# RPi_SPI_outputs_v01.net
KiCad netlist of a schematic drawn in EAGLE
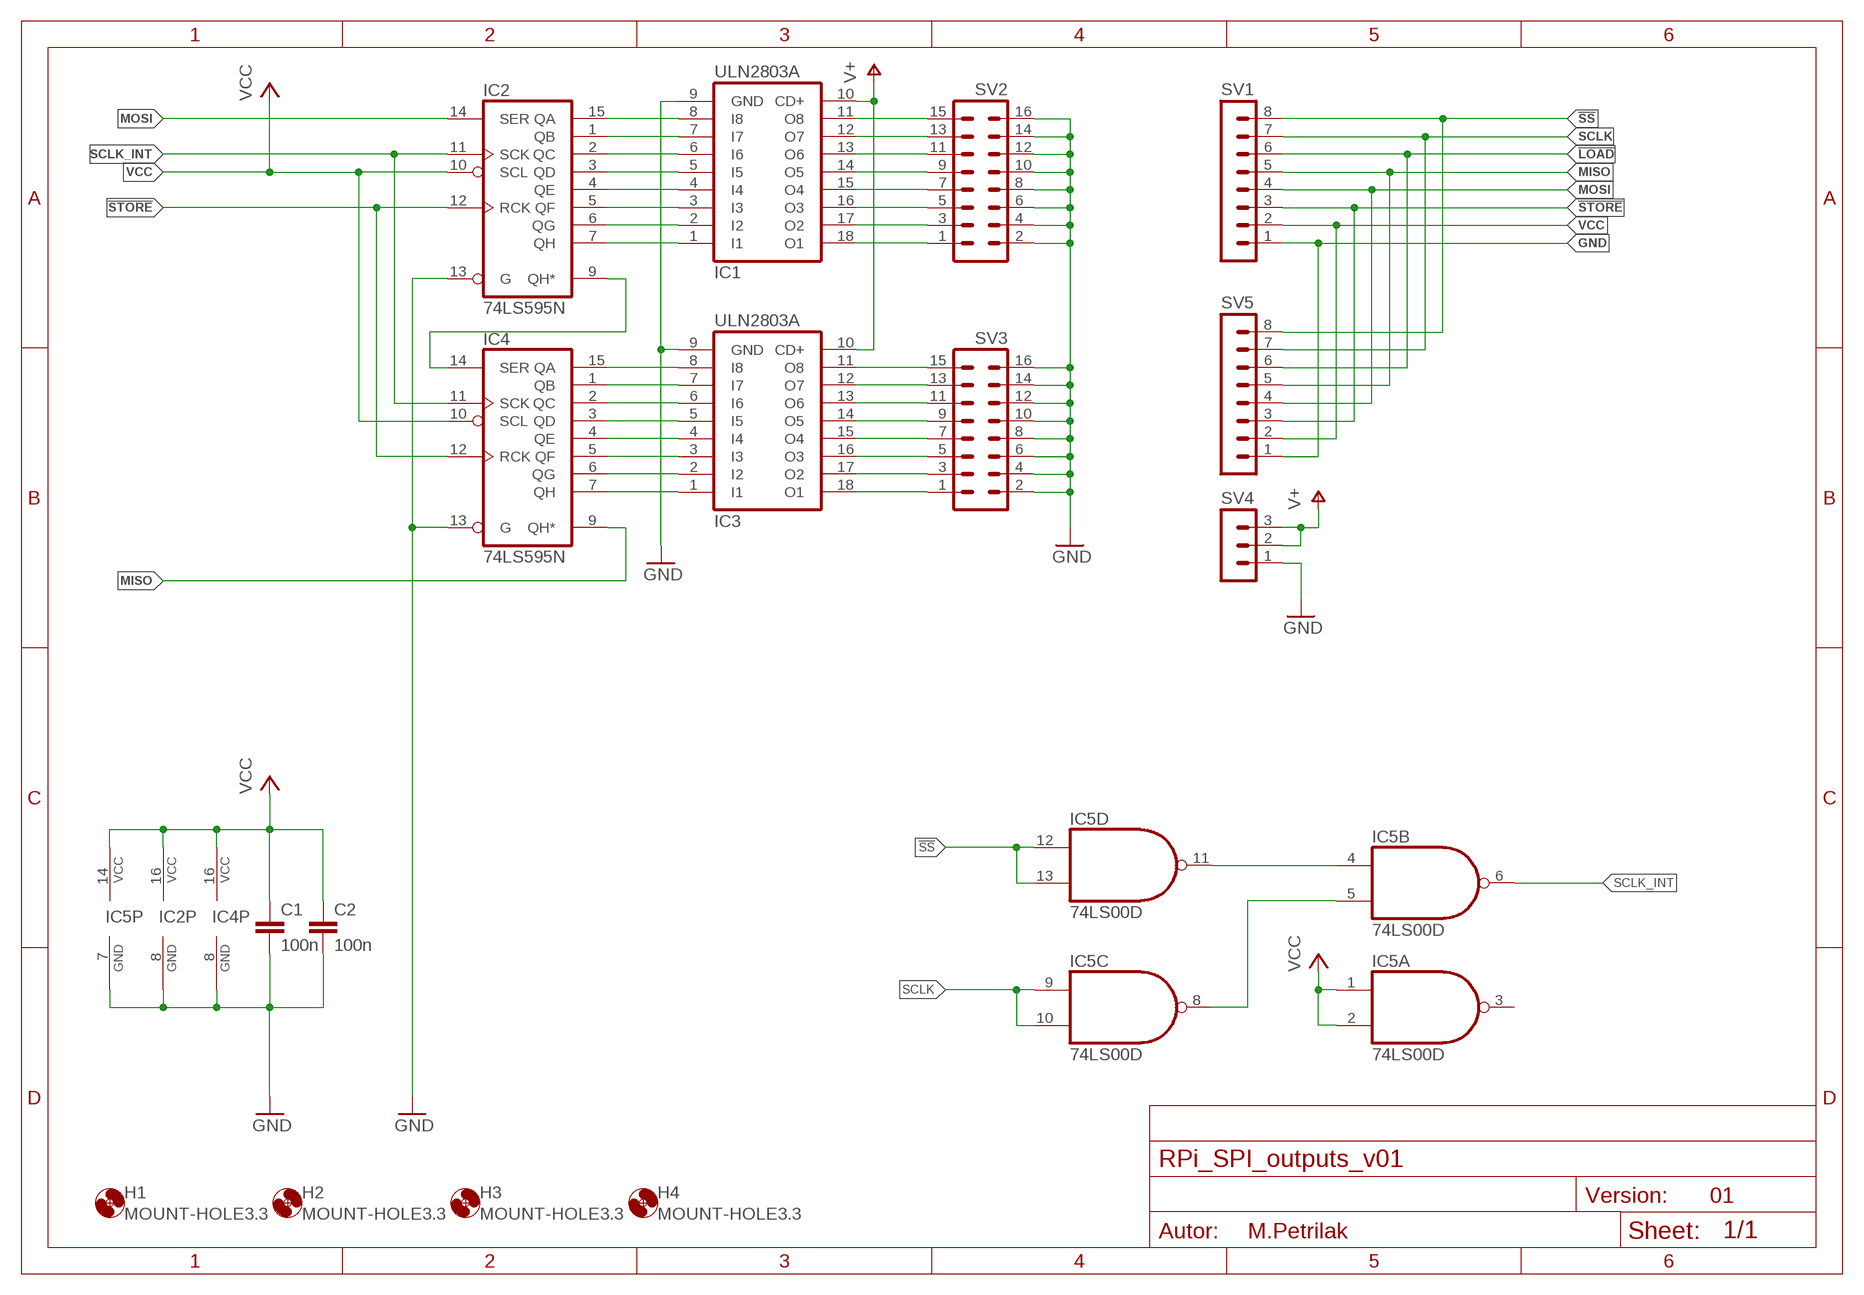
[diagram p0: schematic, sheet 1]

(export (version "E")
  (design (tool "Eeschema 10.0.6"))
  (components
    (comp (ref "C1")
      (value "100n")
      (footprint "eagle-import:C1206")
      (libsource (lib "eagle-import") (part "C-EUC1206"))
    )
    (comp (ref "C2")
      (value "100n")
      (footprint "eagle-import:C1206")
      (libsource (lib "eagle-import") (part "C-EUC1206"))
    )
    (comp (ref "H1")
      (value "MOUNT-HOLE3.3")
      (footprint "eagle-import:3,3")
      (libsource (lib "eagle-import") (part "MOUNT-HOLE3.3"))
    )
    (comp (ref "H2")
      (value "MOUNT-HOLE3.3")
      (footprint "eagle-import:3,3")
      (libsource (lib "eagle-import") (part "MOUNT-HOLE3.3"))
    )
    (comp (ref "H3")
      (value "MOUNT-HOLE3.3")
      (footprint "eagle-import:3,3")
      (libsource (lib "eagle-import") (part "MOUNT-HOLE3.3"))
    )
    (comp (ref "H4")
      (value "MOUNT-HOLE3.3")
      (footprint "eagle-import:3,3")
      (libsource (lib "eagle-import") (part "MOUNT-HOLE3.3"))
    )
    (comp (ref "IC1")
      (value "ULN2803A")
      (footprint "eagle-import:DIL18")
      (libsource (lib "eagle-import") (part "ULN2803A"))
    )
    (comp (ref "IC2")
      (value "74LS595N")
      (footprint "eagle-import:DIL16")
      (libsource (lib "eagle-import") (part "74595NLS"))
    )
    (comp (ref "IC3")
      (value "ULN2803A")
      (footprint "eagle-import:DIL18")
      (libsource (lib "eagle-import") (part "ULN2803A"))
    )
    (comp (ref "IC4")
      (value "74LS595N")
      (footprint "eagle-import:DIL16")
      (libsource (lib "eagle-import") (part "74595NLS"))
    )
    (comp (ref "IC5")
      (value "74LS00D")
      (footprint "eagle-import:SO14")
      (libsource (lib "eagle-import") (part "7400DLS"))
    )
    (comp (ref "SV1")
      (value "MA08-1")
      (footprint "eagle-import:MA08-1")
      (libsource (lib "eagle-import") (part "MA08-1"))
    )
    (comp (ref "SV2")
      (value "MA08-2-OP")
      (footprint "eagle-import:MA08-2-OP")
      (libsource (lib "eagle-import") (part "MA08-2-OP"))
    )
    (comp (ref "SV3")
      (value "MA08-2-OP")
      (footprint "eagle-import:MA08-2-OP")
      (libsource (lib "eagle-import") (part "MA08-2-OP"))
    )
    (comp (ref "SV4")
      (value "MA03-1_NO")
      (footprint "eagle-import:MA03-1_NO")
      (libsource (lib "eagle-import") (part "MA03-1_NO"))
    )
    (comp (ref "SV5")
      (value "MA08-1")
      (footprint "eagle-import:MA08-1")
      (libsource (lib "eagle-import") (part "MA08-1"))
    )
  )
  (nets
    (net (code "1") (name "/~{LOAD}") (class "Default")
      (node (ref "SV1") (pin "6") (pinfunction "6_6") (pintype "passive"))
      (node (ref "SV5") (pin "6") (pinfunction "6_6") (pintype "passive"))
    )
    (net (code "2") (name "/~{SS}") (class "Default")
      (node (ref "IC5") (pin "12") (pinfunction "I0_12") (pintype "input"))
      (node (ref "IC5") (pin "13") (pinfunction "I1_13") (pintype "input"))
      (node (ref "SV1") (pin "8") (pinfunction "8_8") (pintype "passive"))
      (node (ref "SV5") (pin "8") (pinfunction "8_8") (pintype "passive"))
    )
    (net (code "3") (name "/~{STORE}") (class "Default")
      (node (ref "IC2") (pin "12") (pinfunction "RCK_12") (pintype "input"))
      (node (ref "IC4") (pin "12") (pinfunction "RCK_12") (pintype "input"))
      (node (ref "SV1") (pin "3") (pinfunction "3_3") (pintype "passive"))
      (node (ref "SV5") (pin "3") (pinfunction "3_3") (pintype "passive"))
    )
    (net (code "4") (name "GND") (class "Default")
      (node (ref "C1") (pin "2") (pinfunction "2_2") (pintype "passive"))
      (node (ref "C2") (pin "2") (pinfunction "2_2") (pintype "passive"))
      (node (ref "IC1") (pin "9") (pinfunction "GND_9") (pintype "power_in"))
      (node (ref "IC2") (pin "13") (pinfunction "G_13") (pintype "input"))
      (node (ref "IC2") (pin "8") (pinfunction "GND_8") (pintype "power_in"))
      (node (ref "IC3") (pin "9") (pinfunction "GND_9") (pintype "power_in"))
      (node (ref "IC4") (pin "13") (pinfunction "G_13") (pintype "input"))
      (node (ref "IC4") (pin "8") (pinfunction "GND_8") (pintype "power_in"))
      (node (ref "IC5") (pin "7") (pinfunction "GND_7") (pintype "power_in"))
      (node (ref "SV1") (pin "1") (pinfunction "1_1") (pintype "passive"))
      (node (ref "SV2") (pin "10") (pinfunction "10_10") (pintype "passive"))
      (node (ref "SV2") (pin "12") (pinfunction "12_12") (pintype "passive"))
      (node (ref "SV2") (pin "14") (pinfunction "14_14") (pintype "passive"))
      (node (ref "SV2") (pin "16") (pinfunction "16_16") (pintype "passive"))
      (node (ref "SV2") (pin "2") (pinfunction "2_2") (pintype "passive"))
      (node (ref "SV2") (pin "4") (pinfunction "4_4") (pintype "passive"))
      (node (ref "SV2") (pin "6") (pinfunction "6_6") (pintype "passive"))
      (node (ref "SV2") (pin "8") (pinfunction "8_8") (pintype "passive"))
      (node (ref "SV3") (pin "10") (pinfunction "10_10") (pintype "passive"))
      (node (ref "SV3") (pin "12") (pinfunction "12_12") (pintype "passive"))
      (node (ref "SV3") (pin "14") (pinfunction "14_14") (pintype "passive"))
      (node (ref "SV3") (pin "16") (pinfunction "16_16") (pintype "passive"))
      (node (ref "SV3") (pin "2") (pinfunction "2_2") (pintype "passive"))
      (node (ref "SV3") (pin "4") (pinfunction "4_4") (pintype "passive"))
      (node (ref "SV3") (pin "6") (pinfunction "6_6") (pintype "passive"))
      (node (ref "SV3") (pin "8") (pinfunction "8_8") (pintype "passive"))
      (node (ref "SV4") (pin "1") (pinfunction "1_1") (pintype "passive"))
      (node (ref "SV5") (pin "1") (pinfunction "1_1") (pintype "passive"))
    )
    (net (code "5") (name "MISO") (class "Default")
      (node (ref "IC4") (pin "9") (pinfunction "QH*_9") (pintype "tri_state"))
      (node (ref "SV1") (pin "5") (pinfunction "5_5") (pintype "passive"))
      (node (ref "SV5") (pin "5") (pinfunction "5_5") (pintype "passive"))
    )
    (net (code "6") (name "MOSI") (class "Default")
      (node (ref "IC2") (pin "14") (pinfunction "SER_14") (pintype "input"))
      (node (ref "SV1") (pin "4") (pinfunction "4_4") (pintype "passive"))
      (node (ref "SV5") (pin "4") (pinfunction "4_4") (pintype "passive"))
    )
    (net (code "7") (name "Net-(IC1-I1)") (class "Default")
      (node (ref "IC1") (pin "1") (pinfunction "I1_1") (pintype "input"))
      (node (ref "IC2") (pin "7") (pinfunction "QH_7") (pintype "tri_state"))
    )
    (net (code "8") (name "Net-(IC1-I2)") (class "Default")
      (node (ref "IC1") (pin "2") (pinfunction "I2_2") (pintype "input"))
      (node (ref "IC2") (pin "6") (pinfunction "QG_6") (pintype "tri_state"))
    )
    (net (code "9") (name "Net-(IC1-I3)") (class "Default")
      (node (ref "IC1") (pin "3") (pinfunction "I3_3") (pintype "input"))
      (node (ref "IC2") (pin "5") (pinfunction "QF_5") (pintype "tri_state"))
    )
    (net (code "10") (name "Net-(IC1-I4)") (class "Default")
      (node (ref "IC1") (pin "4") (pinfunction "I4_4") (pintype "input"))
      (node (ref "IC2") (pin "4") (pinfunction "QE_4") (pintype "tri_state"))
    )
    (net (code "11") (name "Net-(IC1-I5)") (class "Default")
      (node (ref "IC1") (pin "5") (pinfunction "I5_5") (pintype "input"))
      (node (ref "IC2") (pin "3") (pinfunction "QD_3") (pintype "tri_state"))
    )
    (net (code "12") (name "Net-(IC1-I6)") (class "Default")
      (node (ref "IC1") (pin "6") (pinfunction "I6_6") (pintype "input"))
      (node (ref "IC2") (pin "2") (pinfunction "QC_2") (pintype "tri_state"))
    )
    (net (code "13") (name "Net-(IC1-I7)") (class "Default")
      (node (ref "IC1") (pin "7") (pinfunction "I7_7") (pintype "input"))
      (node (ref "IC2") (pin "1") (pinfunction "QB_1") (pintype "tri_state"))
    )
    (net (code "14") (name "Net-(IC1-I8)") (class "Default")
      (node (ref "IC1") (pin "8") (pinfunction "I8_8") (pintype "input"))
      (node (ref "IC2") (pin "15") (pinfunction "QA_15") (pintype "tri_state"))
    )
    (net (code "15") (name "Net-(IC1-O1)") (class "Default")
      (node (ref "IC1") (pin "18") (pinfunction "O1_18") (pintype "open_collector"))
      (node (ref "SV2") (pin "1") (pinfunction "1_1") (pintype "passive"))
    )
    (net (code "16") (name "Net-(IC1-O2)") (class "Default")
      (node (ref "IC1") (pin "17") (pinfunction "O2_17") (pintype "open_collector"))
      (node (ref "SV2") (pin "3") (pinfunction "3_3") (pintype "passive"))
    )
    (net (code "17") (name "Net-(IC1-O3)") (class "Default")
      (node (ref "IC1") (pin "16") (pinfunction "O3_16") (pintype "open_collector"))
      (node (ref "SV2") (pin "5") (pinfunction "5_5") (pintype "passive"))
    )
    (net (code "18") (name "Net-(IC1-O4)") (class "Default")
      (node (ref "IC1") (pin "15") (pinfunction "O4_15") (pintype "open_collector"))
      (node (ref "SV2") (pin "7") (pinfunction "7_7") (pintype "passive"))
    )
    (net (code "19") (name "Net-(IC1-O5)") (class "Default")
      (node (ref "IC1") (pin "14") (pinfunction "O5_14") (pintype "open_collector"))
      (node (ref "SV2") (pin "9") (pinfunction "9_9") (pintype "passive"))
    )
    (net (code "20") (name "Net-(IC1-O6)") (class "Default")
      (node (ref "IC1") (pin "13") (pinfunction "O6_13") (pintype "open_collector"))
      (node (ref "SV2") (pin "11") (pinfunction "11_11") (pintype "passive"))
    )
    (net (code "21") (name "Net-(IC1-O7)") (class "Default")
      (node (ref "IC1") (pin "12") (pinfunction "O7_12") (pintype "open_collector"))
      (node (ref "SV2") (pin "13") (pinfunction "13_13") (pintype "passive"))
    )
    (net (code "22") (name "Net-(IC1-O8)") (class "Default")
      (node (ref "IC1") (pin "11") (pinfunction "O8_11") (pintype "open_collector"))
      (node (ref "SV2") (pin "15") (pinfunction "15_15") (pintype "passive"))
    )
    (net (code "23") (name "Net-(IC2A-QH*)") (class "Default")
      (node (ref "IC2") (pin "9") (pinfunction "QH*_9") (pintype "tri_state"))
      (node (ref "IC4") (pin "14") (pinfunction "SER_14") (pintype "input"))
    )
    (net (code "24") (name "Net-(IC3-I1)") (class "Default")
      (node (ref "IC3") (pin "1") (pinfunction "I1_1") (pintype "input"))
      (node (ref "IC4") (pin "7") (pinfunction "QH_7") (pintype "tri_state"))
    )
    (net (code "25") (name "Net-(IC3-I2)") (class "Default")
      (node (ref "IC3") (pin "2") (pinfunction "I2_2") (pintype "input"))
      (node (ref "IC4") (pin "6") (pinfunction "QG_6") (pintype "tri_state"))
    )
    (net (code "26") (name "Net-(IC3-I3)") (class "Default")
      (node (ref "IC3") (pin "3") (pinfunction "I3_3") (pintype "input"))
      (node (ref "IC4") (pin "5") (pinfunction "QF_5") (pintype "tri_state"))
    )
    (net (code "27") (name "Net-(IC3-I4)") (class "Default")
      (node (ref "IC3") (pin "4") (pinfunction "I4_4") (pintype "input"))
      (node (ref "IC4") (pin "4") (pinfunction "QE_4") (pintype "tri_state"))
    )
    (net (code "28") (name "Net-(IC3-I5)") (class "Default")
      (node (ref "IC3") (pin "5") (pinfunction "I5_5") (pintype "input"))
      (node (ref "IC4") (pin "3") (pinfunction "QD_3") (pintype "tri_state"))
    )
    (net (code "29") (name "Net-(IC3-I6)") (class "Default")
      (node (ref "IC3") (pin "6") (pinfunction "I6_6") (pintype "input"))
      (node (ref "IC4") (pin "2") (pinfunction "QC_2") (pintype "tri_state"))
    )
    (net (code "30") (name "Net-(IC3-I7)") (class "Default")
      (node (ref "IC3") (pin "7") (pinfunction "I7_7") (pintype "input"))
      (node (ref "IC4") (pin "1") (pinfunction "QB_1") (pintype "tri_state"))
    )
    (net (code "31") (name "Net-(IC3-I8)") (class "Default")
      (node (ref "IC3") (pin "8") (pinfunction "I8_8") (pintype "input"))
      (node (ref "IC4") (pin "15") (pinfunction "QA_15") (pintype "tri_state"))
    )
    (net (code "32") (name "Net-(IC3-O1)") (class "Default")
      (node (ref "IC3") (pin "18") (pinfunction "O1_18") (pintype "open_collector"))
      (node (ref "SV3") (pin "1") (pinfunction "1_1") (pintype "passive"))
    )
    (net (code "33") (name "Net-(IC3-O2)") (class "Default")
      (node (ref "IC3") (pin "17") (pinfunction "O2_17") (pintype "open_collector"))
      (node (ref "SV3") (pin "3") (pinfunction "3_3") (pintype "passive"))
    )
    (net (code "34") (name "Net-(IC3-O3)") (class "Default")
      (node (ref "IC3") (pin "16") (pinfunction "O3_16") (pintype "open_collector"))
      (node (ref "SV3") (pin "5") (pinfunction "5_5") (pintype "passive"))
    )
    (net (code "35") (name "Net-(IC3-O4)") (class "Default")
      (node (ref "IC3") (pin "15") (pinfunction "O4_15") (pintype "open_collector"))
      (node (ref "SV3") (pin "7") (pinfunction "7_7") (pintype "passive"))
    )
    (net (code "36") (name "Net-(IC3-O5)") (class "Default")
      (node (ref "IC3") (pin "14") (pinfunction "O5_14") (pintype "open_collector"))
      (node (ref "SV3") (pin "9") (pinfunction "9_9") (pintype "passive"))
    )
    (net (code "37") (name "Net-(IC3-O6)") (class "Default")
      (node (ref "IC3") (pin "13") (pinfunction "O6_13") (pintype "open_collector"))
      (node (ref "SV3") (pin "11") (pinfunction "11_11") (pintype "passive"))
    )
    (net (code "38") (name "Net-(IC3-O7)") (class "Default")
      (node (ref "IC3") (pin "12") (pinfunction "O7_12") (pintype "open_collector"))
      (node (ref "SV3") (pin "13") (pinfunction "13_13") (pintype "passive"))
    )
    (net (code "39") (name "Net-(IC3-O8)") (class "Default")
      (node (ref "IC3") (pin "11") (pinfunction "O8_11") (pintype "open_collector"))
      (node (ref "SV3") (pin "15") (pinfunction "15_15") (pintype "passive"))
    )
    (net (code "40") (name "Net-(IC5B-I0)") (class "Default")
      (node (ref "IC5") (pin "11") (pinfunction "O_11") (pintype "output"))
      (node (ref "IC5") (pin "4") (pinfunction "I0_4") (pintype "input"))
    )
    (net (code "41") (name "Net-(IC5B-I1)") (class "Default")
      (node (ref "IC5") (pin "5") (pinfunction "I1_5") (pintype "input"))
      (node (ref "IC5") (pin "8") (pinfunction "O_8") (pintype "output"))
    )
    (net (code "42") (name "SCLK") (class "Default")
      (node (ref "IC5") (pin "10") (pinfunction "I1_10") (pintype "input"))
      (node (ref "IC5") (pin "9") (pinfunction "I0_9") (pintype "input"))
      (node (ref "SV1") (pin "7") (pinfunction "7_7") (pintype "passive"))
      (node (ref "SV5") (pin "7") (pinfunction "7_7") (pintype "passive"))
    )
    (net (code "43") (name "SCLK_INT") (class "Default")
      (node (ref "IC2") (pin "11") (pinfunction "SCK_11") (pintype "input"))
      (node (ref "IC4") (pin "11") (pinfunction "SCK_11") (pintype "input"))
      (node (ref "IC5") (pin "6") (pinfunction "O_6") (pintype "output"))
    )
    (net (code "44") (name "V+") (class "Default")
      (node (ref "IC1") (pin "10") (pinfunction "CD+_10") (pintype "passive"))
      (node (ref "IC3") (pin "10") (pinfunction "CD+_10") (pintype "passive"))
      (node (ref "SV4") (pin "2") (pinfunction "2_2") (pintype "passive"))
      (node (ref "SV4") (pin "3") (pinfunction "3_3") (pintype "passive"))
    )
    (net (code "45") (name "VCC") (class "Default")
      (node (ref "C1") (pin "1") (pinfunction "1_1") (pintype "passive"))
      (node (ref "C2") (pin "1") (pinfunction "1_1") (pintype "passive"))
      (node (ref "IC2") (pin "10") (pinfunction "SCL_10") (pintype "input"))
      (node (ref "IC2") (pin "16") (pinfunction "VCC_16") (pintype "power_in"))
      (node (ref "IC4") (pin "10") (pinfunction "SCL_10") (pintype "input"))
      (node (ref "IC4") (pin "16") (pinfunction "VCC_16") (pintype "power_in"))
      (node (ref "IC5") (pin "1") (pinfunction "I0_1") (pintype "input"))
      (node (ref "IC5") (pin "14") (pinfunction "VCC_14") (pintype "power_in"))
      (node (ref "IC5") (pin "2") (pinfunction "I1_2") (pintype "input"))
      (node (ref "SV1") (pin "2") (pinfunction "2_2") (pintype "passive"))
      (node (ref "SV5") (pin "2") (pinfunction "2_2") (pintype "passive"))
    )
    (net (code "46") (name "unconnected-(IC5A-O-Pad3)") (class "Default")
      (node (ref "IC5") (pin "3") (pinfunction "O_3") (pintype "output"))
    )
  )
)
